# motores_01.net
KiCad netlist of a schematic drawn in EAGLE
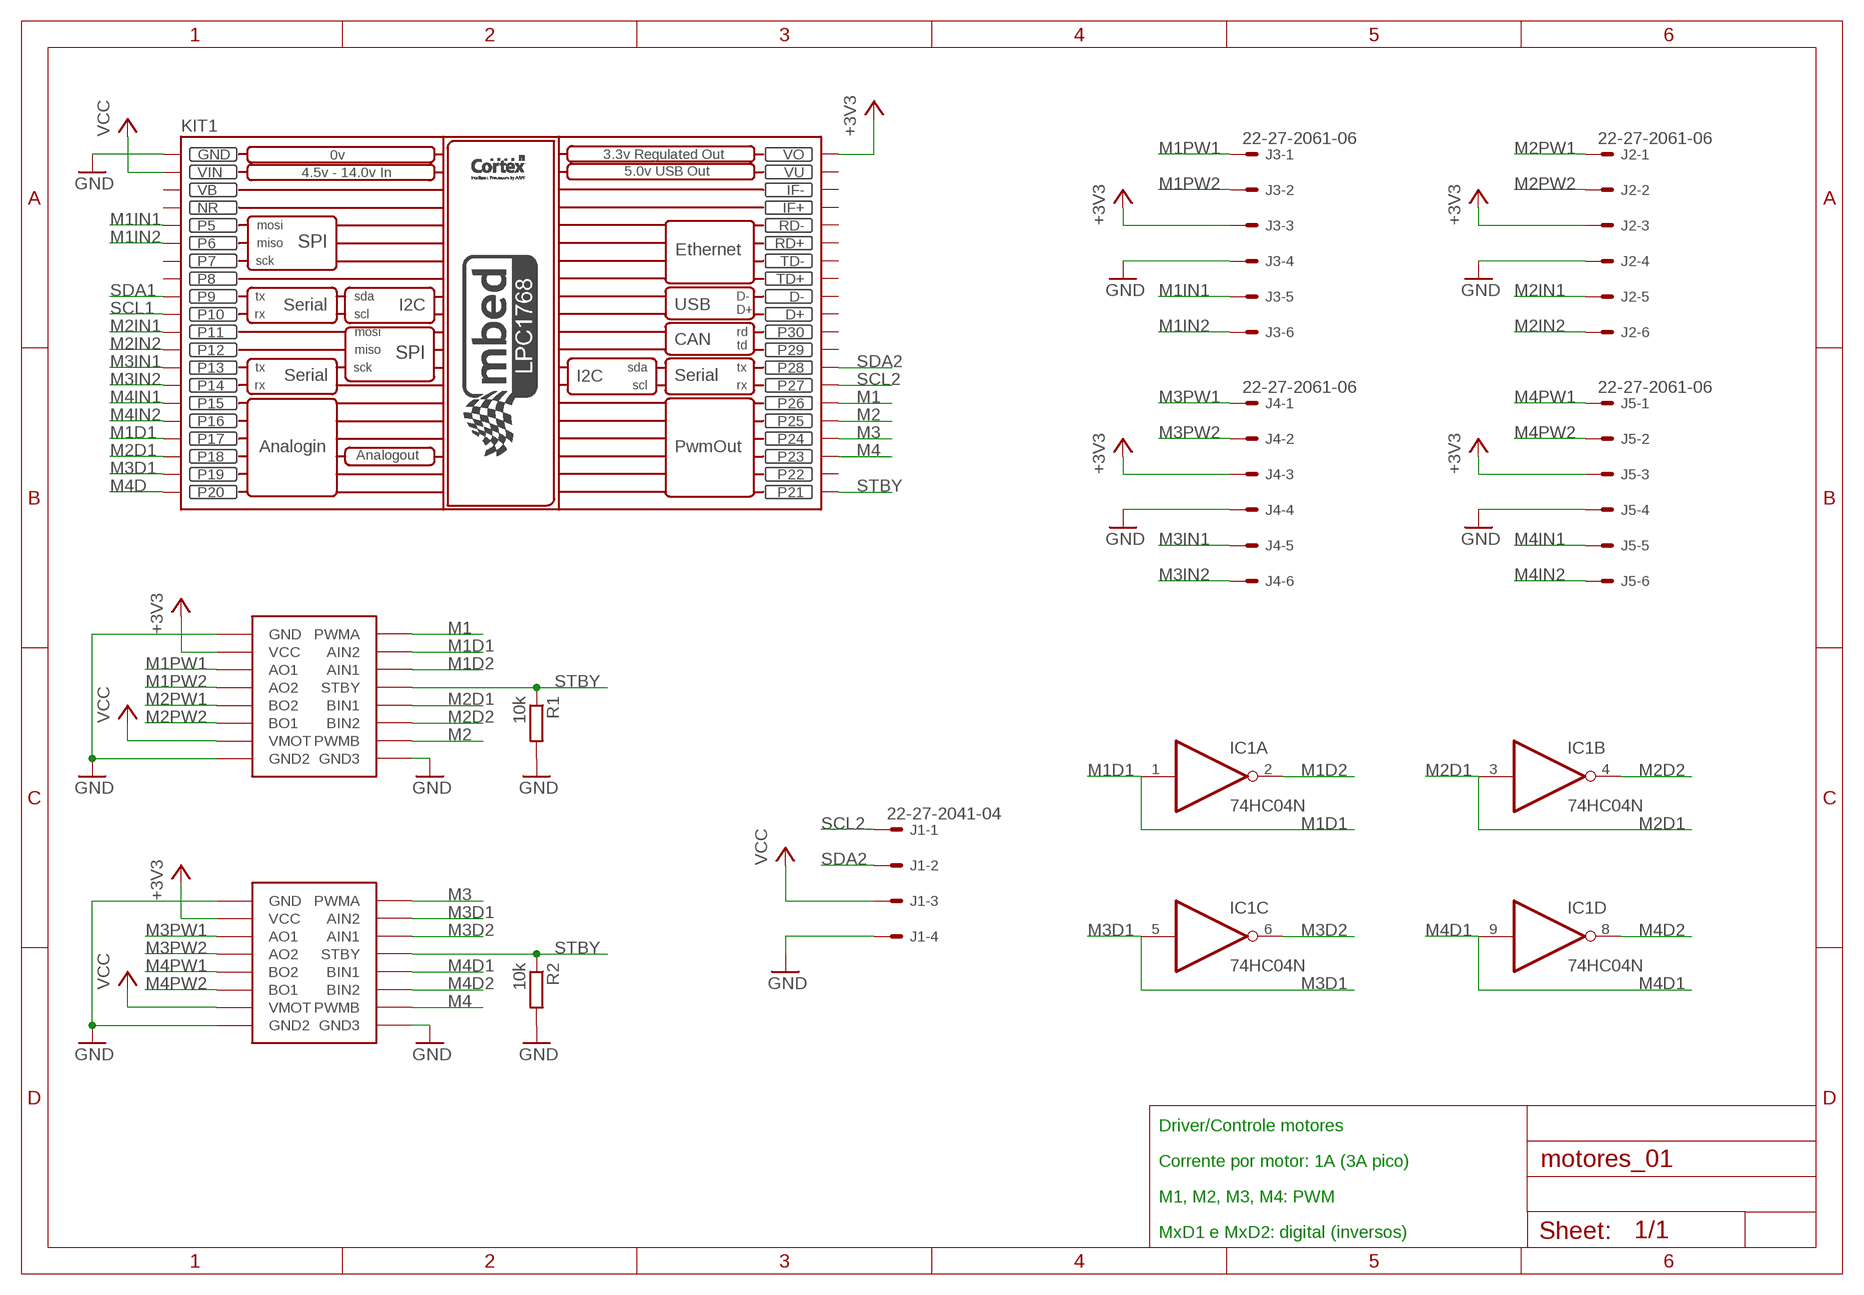
[diagram p0: schematic, sheet 1]

(export (version "E")
  (design (tool "Eeschema 10.0.6"))
  (components
    (comp (ref "IC1")
      (value "74HC04N")
      (footprint "eagle-import:DIL14")
      (libsource (lib "eagle-import") (part "7404NHC"))
    )
    (comp (ref "J1")
      (value "22-27-2041-04")
      (footprint "eagle-import:6410-04")
      (libsource (lib "eagle-import") (part "22-?-0427-2041"))
    )
    (comp (ref "J2")
      (value "22-27-2061-06")
      (footprint "eagle-import:6410-06")
      (libsource (lib "eagle-import") (part "22-?-0627-2061"))
    )
    (comp (ref "J3")
      (value "22-27-2061-06")
      (footprint "eagle-import:6410-06")
      (libsource (lib "eagle-import") (part "22-?-0627-2061"))
    )
    (comp (ref "J4")
      (value "22-27-2061-06")
      (footprint "eagle-import:6410-06")
      (libsource (lib "eagle-import") (part "22-?-0627-2061"))
    )
    (comp (ref "J5")
      (value "22-27-2061-06")
      (footprint "eagle-import:6410-06")
      (libsource (lib "eagle-import") (part "22-?-0627-2061"))
    )
    (comp (ref "KIT1")
      (value "MBED_NXP_LPC1768")
      (footprint "eagle-import:MBED-KIT")
      (libsource (lib "eagle-import") (part "MBED_NXP_LPC1768"))
    )
    (comp (ref "R1")
      (value "10k")
      (footprint "eagle-import:0204_7")
      (libsource (lib "eagle-import") (part "R-EU_0204/7"))
    )
    (comp (ref "R2")
      (value "10k")
      (footprint "eagle-import:0204_7")
      (libsource (lib "eagle-import") (part "R-EU_0204/7"))
    )
    (comp (ref "U$1")
      (value "MOTORDRIVER")
      (footprint "eagle-import:16PH")
      (libsource (lib "eagle-import") (part "MOTORDRIVER"))
    )
    (comp (ref "U$2")
      (value "MOTORDRIVER")
      (footprint "eagle-import:16PH")
      (libsource (lib "eagle-import") (part "MOTORDRIVER"))
    )
  )
  (nets
    (net (code "1") (name "+3V3") (class "Default")
      (node (ref "J2") (pin "3") (pinfunction "S_3") (pintype "passive"))
      (node (ref "J3") (pin "3") (pinfunction "S_3") (pintype "passive"))
      (node (ref "J4") (pin "3") (pinfunction "S_3") (pintype "passive"))
      (node (ref "J5") (pin "3") (pinfunction "S_3") (pintype "passive"))
      (node (ref "KIT1") (pin "VOUT") (pinfunction "VO_VOUT") (pintype "power_in"))
      (node (ref "U$1") (pin "P$2") (pinfunction "VCC_P$2") (pintype "bidirectional"))
      (node (ref "U$2") (pin "P$2") (pinfunction "VCC_P$2") (pintype "bidirectional"))
    )
    (net (code "2") (name "/M1") (class "Default")
      (node (ref "KIT1") (pin "P$26") (pinfunction "P26_P$26") (pintype "bidirectional"))
      (node (ref "U$1") (pin "P$16") (pinfunction "PWMA_P$16") (pintype "bidirectional"))
    )
    (net (code "3") (name "/M1D1") (class "Default")
      (node (ref "IC1") (pin "1") (pinfunction "I_1") (pintype "input"))
      (node (ref "KIT1") (pin "P$17") (pinfunction "P17_P$17") (pintype "bidirectional"))
      (node (ref "U$1") (pin "P$15") (pinfunction "AIN2_P$15") (pintype "bidirectional"))
    )
    (net (code "4") (name "/M1D2") (class "Default")
      (node (ref "IC1") (pin "2") (pinfunction "O_2") (pintype "output"))
      (node (ref "U$1") (pin "P$14") (pinfunction "AIN1_P$14") (pintype "bidirectional"))
    )
    (net (code "5") (name "/M1IN1") (class "Default")
      (node (ref "J3") (pin "5") (pinfunction "S_5") (pintype "passive"))
      (node (ref "KIT1") (pin "P$5") (pinfunction "P5_P$5") (pintype "bidirectional"))
    )
    (net (code "6") (name "/M1IN2") (class "Default")
      (node (ref "J3") (pin "6") (pinfunction "S_6") (pintype "passive"))
      (node (ref "KIT1") (pin "P$6") (pinfunction "P6_P$6") (pintype "bidirectional"))
    )
    (net (code "7") (name "/M1PW1") (class "Default")
      (node (ref "J3") (pin "1") (pinfunction "S_1") (pintype "passive"))
      (node (ref "U$1") (pin "P$3") (pinfunction "AO1_P$3") (pintype "bidirectional"))
    )
    (net (code "8") (name "/M1PW2") (class "Default")
      (node (ref "J3") (pin "2") (pinfunction "S_2") (pintype "passive"))
      (node (ref "U$1") (pin "P$4") (pinfunction "AO2_P$4") (pintype "bidirectional"))
    )
    (net (code "9") (name "/M2") (class "Default")
      (node (ref "KIT1") (pin "P$25") (pinfunction "P25_P$25") (pintype "bidirectional"))
      (node (ref "U$1") (pin "P$10") (pinfunction "PWMB_P$10") (pintype "bidirectional"))
    )
    (net (code "10") (name "/M2D1") (class "Default")
      (node (ref "IC1") (pin "3") (pinfunction "I_3") (pintype "input"))
      (node (ref "KIT1") (pin "P$18") (pinfunction "P18_P$18") (pintype "bidirectional"))
      (node (ref "U$1") (pin "P$12") (pinfunction "BIN1_P$12") (pintype "bidirectional"))
    )
    (net (code "11") (name "/M2D2") (class "Default")
      (node (ref "IC1") (pin "4") (pinfunction "O_4") (pintype "output"))
      (node (ref "U$1") (pin "P$11") (pinfunction "BIN2_P$11") (pintype "bidirectional"))
    )
    (net (code "12") (name "/M2IN1") (class "Default")
      (node (ref "J2") (pin "5") (pinfunction "S_5") (pintype "passive"))
      (node (ref "KIT1") (pin "P$11") (pinfunction "P11_P$11") (pintype "bidirectional"))
    )
    (net (code "13") (name "/M2IN2") (class "Default")
      (node (ref "J2") (pin "6") (pinfunction "S_6") (pintype "passive"))
      (node (ref "KIT1") (pin "P$12") (pinfunction "P12_P$12") (pintype "bidirectional"))
    )
    (net (code "14") (name "/M2PW1") (class "Default")
      (node (ref "J2") (pin "1") (pinfunction "S_1") (pintype "passive"))
      (node (ref "U$1") (pin "P$5") (pinfunction "BO2_P$5") (pintype "bidirectional"))
    )
    (net (code "15") (name "/M2PW2") (class "Default")
      (node (ref "J2") (pin "2") (pinfunction "S_2") (pintype "passive"))
      (node (ref "U$1") (pin "P$6") (pinfunction "BO1_P$6") (pintype "bidirectional"))
    )
    (net (code "16") (name "/M3") (class "Default")
      (node (ref "KIT1") (pin "P$24") (pinfunction "P24_P$24") (pintype "bidirectional"))
      (node (ref "U$2") (pin "P$16") (pinfunction "PWMA_P$16") (pintype "bidirectional"))
    )
    (net (code "17") (name "/M3D1") (class "Default")
      (node (ref "IC1") (pin "5") (pinfunction "I_5") (pintype "input"))
      (node (ref "KIT1") (pin "P$19") (pinfunction "P19_P$19") (pintype "bidirectional"))
      (node (ref "U$2") (pin "P$15") (pinfunction "AIN2_P$15") (pintype "bidirectional"))
    )
    (net (code "18") (name "/M3D2") (class "Default")
      (node (ref "IC1") (pin "6") (pinfunction "O_6") (pintype "output"))
      (node (ref "U$2") (pin "P$14") (pinfunction "AIN1_P$14") (pintype "bidirectional"))
    )
    (net (code "19") (name "/M3IN1") (class "Default")
      (node (ref "J4") (pin "5") (pinfunction "S_5") (pintype "passive"))
      (node (ref "KIT1") (pin "P$13") (pinfunction "P13_P$13") (pintype "bidirectional"))
    )
    (net (code "20") (name "/M3IN2") (class "Default")
      (node (ref "J4") (pin "6") (pinfunction "S_6") (pintype "passive"))
      (node (ref "KIT1") (pin "P$14") (pinfunction "P14_P$14") (pintype "bidirectional"))
    )
    (net (code "21") (name "/M3PW1") (class "Default")
      (node (ref "J4") (pin "1") (pinfunction "S_1") (pintype "passive"))
      (node (ref "U$2") (pin "P$3") (pinfunction "AO1_P$3") (pintype "bidirectional"))
    )
    (net (code "22") (name "/M3PW2") (class "Default")
      (node (ref "J4") (pin "2") (pinfunction "S_2") (pintype "passive"))
      (node (ref "U$2") (pin "P$4") (pinfunction "AO2_P$4") (pintype "bidirectional"))
    )
    (net (code "23") (name "/M4") (class "Default")
      (node (ref "KIT1") (pin "P$23") (pinfunction "P23_P$23") (pintype "bidirectional"))
      (node (ref "U$2") (pin "P$10") (pinfunction "PWMB_P$10") (pintype "bidirectional"))
    )
    (net (code "24") (name "/M4D") (class "Default")
      (node (ref "KIT1") (pin "P$20") (pinfunction "P20_P$20") (pintype "bidirectional"))
    )
    (net (code "25") (name "/M4D1") (class "Default")
      (node (ref "IC1") (pin "9") (pinfunction "I_9") (pintype "input"))
      (node (ref "U$2") (pin "P$12") (pinfunction "BIN1_P$12") (pintype "bidirectional"))
    )
    (net (code "26") (name "/M4D2") (class "Default")
      (node (ref "IC1") (pin "8") (pinfunction "O_8") (pintype "output"))
      (node (ref "U$2") (pin "P$11") (pinfunction "BIN2_P$11") (pintype "bidirectional"))
    )
    (net (code "27") (name "/M4IN1") (class "Default")
      (node (ref "J5") (pin "5") (pinfunction "S_5") (pintype "passive"))
      (node (ref "KIT1") (pin "P$15") (pinfunction "P15_P$15") (pintype "bidirectional"))
    )
    (net (code "28") (name "/M4IN2") (class "Default")
      (node (ref "J5") (pin "6") (pinfunction "S_6") (pintype "passive"))
      (node (ref "KIT1") (pin "P$16") (pinfunction "P16_P$16") (pintype "bidirectional"))
    )
    (net (code "29") (name "/M4PW1") (class "Default")
      (node (ref "J5") (pin "1") (pinfunction "S_1") (pintype "passive"))
      (node (ref "U$2") (pin "P$5") (pinfunction "BO2_P$5") (pintype "bidirectional"))
    )
    (net (code "30") (name "/M4PW2") (class "Default")
      (node (ref "J5") (pin "2") (pinfunction "S_2") (pintype "passive"))
      (node (ref "U$2") (pin "P$6") (pinfunction "BO1_P$6") (pintype "bidirectional"))
    )
    (net (code "31") (name "/NR") (class "Default")
      (node (ref "KIT1") (pin "NR") (pinfunction "NR_NR") (pintype "power_in"))
    )
    (net (code "32") (name "/SCL1") (class "Default")
      (node (ref "KIT1") (pin "P$10") (pinfunction "P10_P$10") (pintype "bidirectional"))
    )
    (net (code "33") (name "/SCL2") (class "Default")
      (node (ref "J1") (pin "1") (pinfunction "S_1") (pintype "passive"))
      (node (ref "KIT1") (pin "P$27") (pinfunction "P27_P$27") (pintype "bidirectional"))
    )
    (net (code "34") (name "/SDA1") (class "Default")
      (node (ref "KIT1") (pin "P$9") (pinfunction "P9_P$9") (pintype "bidirectional"))
    )
    (net (code "35") (name "/SDA2") (class "Default")
      (node (ref "J1") (pin "2") (pinfunction "S_2") (pintype "passive"))
      (node (ref "KIT1") (pin "P$28") (pinfunction "P28_P$28") (pintype "bidirectional"))
    )
    (net (code "36") (name "/STBY") (class "Default")
      (node (ref "KIT1") (pin "P$21") (pinfunction "P21_P$21") (pintype "bidirectional"))
      (node (ref "R1") (pin "1") (pinfunction "1_1") (pintype "passive"))
      (node (ref "R2") (pin "1") (pinfunction "1_1") (pintype "passive"))
      (node (ref "U$1") (pin "P$13") (pinfunction "STBY_P$13") (pintype "bidirectional"))
      (node (ref "U$2") (pin "P$13") (pinfunction "STBY_P$13") (pintype "bidirectional"))
    )
    (net (code "37") (name "/VB") (class "Default")
      (node (ref "KIT1") (pin "VB") (pinfunction "VB_VB") (pintype "power_in"))
    )
    (net (code "38") (name "/VU") (class "Default")
      (node (ref "KIT1") (pin "VU") (pinfunction "VU_VU") (pintype "power_in"))
    )
    (net (code "39") (name "GND") (class "Default")
      (node (ref "J1") (pin "4") (pinfunction "S_4") (pintype "passive"))
      (node (ref "J2") (pin "4") (pinfunction "S_4") (pintype "passive"))
      (node (ref "J3") (pin "4") (pinfunction "S_4") (pintype "passive"))
      (node (ref "J4") (pin "4") (pinfunction "S_4") (pintype "passive"))
      (node (ref "J5") (pin "4") (pinfunction "S_4") (pintype "passive"))
      (node (ref "KIT1") (pin "GND") (pinfunction "GND_GND") (pintype "power_in"))
      (node (ref "R1") (pin "2") (pinfunction "2_2") (pintype "passive"))
      (node (ref "R2") (pin "2") (pinfunction "2_2") (pintype "passive"))
      (node (ref "U$1") (pin "P$1") (pinfunction "GND_P$1") (pintype "bidirectional"))
      (node (ref "U$1") (pin "P$8") (pinfunction "GND2_P$8") (pintype "bidirectional"))
      (node (ref "U$1") (pin "P$9") (pinfunction "GND3_P$9") (pintype "bidirectional"))
      (node (ref "U$2") (pin "P$1") (pinfunction "GND_P$1") (pintype "bidirectional"))
      (node (ref "U$2") (pin "P$8") (pinfunction "GND2_P$8") (pintype "bidirectional"))
      (node (ref "U$2") (pin "P$9") (pinfunction "GND3_P$9") (pintype "bidirectional"))
    )
    (net (code "40") (name "VCC") (class "Default")
      (node (ref "J1") (pin "3") (pinfunction "S_3") (pintype "passive"))
      (node (ref "KIT1") (pin "VIN") (pinfunction "VIN_VIN") (pintype "power_in"))
      (node (ref "U$1") (pin "P$7") (pinfunction "VMOT_P$7") (pintype "bidirectional"))
      (node (ref "U$2") (pin "P$7") (pinfunction "VMOT_P$7") (pintype "bidirectional"))
    )
    (net (code "41") (name "unconnected-(KIT1-P7-PadP$7)") (class "Default")
      (node (ref "KIT1") (pin "P$7") (pinfunction "P7_P$7") (pintype "bidirectional"))
    )
    (net (code "42") (name "unconnected-(KIT1-P8-PadP$8)") (class "Default")
      (node (ref "KIT1") (pin "P$8") (pinfunction "P8_P$8") (pintype "bidirectional"))
    )
    (net (code "43") (name "unconnected-(KIT1-P22-PadP$22)") (class "Default")
      (node (ref "KIT1") (pin "P$22") (pinfunction "P22_P$22") (pintype "bidirectional"))
    )
    (net (code "44") (name "unconnected-(KIT1-P29-PadP$29)") (class "Default")
      (node (ref "KIT1") (pin "P$29") (pinfunction "P29_P$29") (pintype "bidirectional"))
    )
    (net (code "45") (name "unconnected-(KIT1-P30-PadP$30)") (class "Default")
      (node (ref "KIT1") (pin "P$30") (pinfunction "P30_P$30") (pintype "bidirectional"))
    )
    (net (code "46") (name "unconnected-(KIT1-PadD+)") (class "Default")
      (node (ref "KIT1") (pin "D+") (pinfunction "D+_D+") (pintype "bidirectional"))
    )
    (net (code "47") (name "unconnected-(KIT1-PadD-)") (class "Default")
      (node (ref "KIT1") (pin "D-") (pinfunction "D-_D-") (pintype "bidirectional"))
    )
    (net (code "48") (name "unconnected-(KIT1-PadIF+)") (class "Default")
      (node (ref "KIT1") (pin "IF+") (pinfunction "IF+_IF+") (pintype "bidirectional"))
    )
    (net (code "49") (name "unconnected-(KIT1-PadIF-)") (class "Default")
      (node (ref "KIT1") (pin "IF-") (pinfunction "IF-_IF-") (pintype "bidirectional"))
    )
    (net (code "50") (name "unconnected-(KIT1-PadRD+)") (class "Default")
      (node (ref "KIT1") (pin "RD+") (pinfunction "RD+_RD+") (pintype "bidirectional"))
    )
    (net (code "51") (name "unconnected-(KIT1-PadRD-)") (class "Default")
      (node (ref "KIT1") (pin "RD-") (pinfunction "RD-_RD-") (pintype "bidirectional"))
    )
    (net (code "52") (name "unconnected-(KIT1-PadTD+)") (class "Default")
      (node (ref "KIT1") (pin "TD+") (pinfunction "TD+_TD+") (pintype "bidirectional"))
    )
    (net (code "53") (name "unconnected-(KIT1-PadTD-)") (class "Default")
      (node (ref "KIT1") (pin "TD-") (pinfunction "TD-_TD-") (pintype "bidirectional"))
    )
  )
)
